# 1_Top_Sheet.net
KiCad netlist of a schematic drawn in Altium Designer
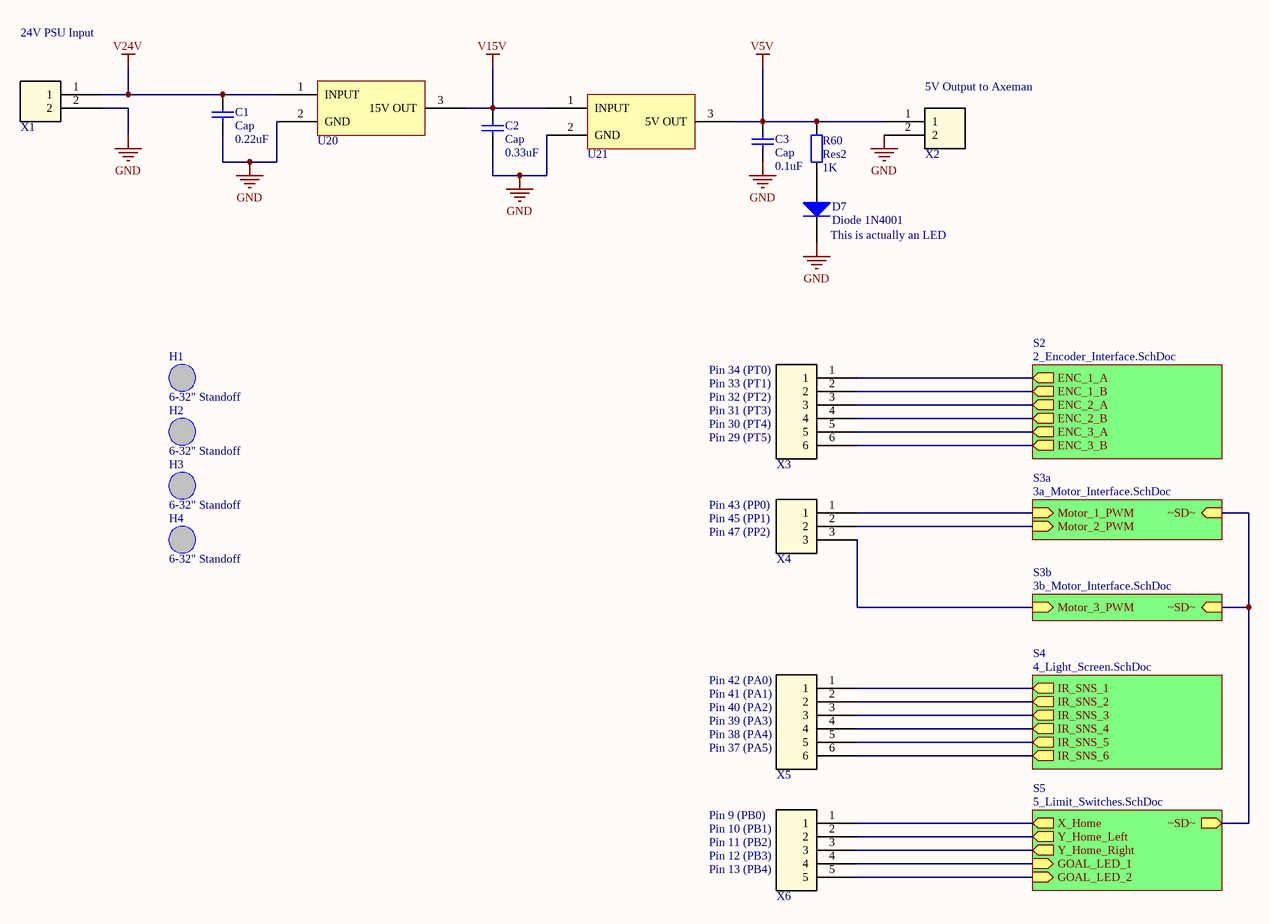
[diagram p0: 1_Top_Sheet.SchDoc]

(export (version "E")
  (design (tool "Eeschema 10.0.6"))
  (components
    (comp (ref "C1")
      (value "Cap")
      (footprint "RAD-0.3")
      (description "Capacitor")
      (fields (field (name "ALTIUM_VALUE") "0.22uF") (field (name "PUBLISHER") "Altium Limited"))
      (libsource (lib "Miscellaneous Devices") (part "Cap"))
    )
    (comp (ref "C2")
      (value "Cap")
      (footprint "RAD-0.3")
      (description "Capacitor")
      (fields (field (name "ALTIUM_VALUE") "0.33uF") (field (name "PUBLISHER") "Altium Limited"))
      (libsource (lib "Miscellaneous Devices") (part "Cap"))
    )
    (comp (ref "C3")
      (value "Cap")
      (footprint "RAD-0.3")
      (description "Capacitor")
      (fields (field (name "ALTIUM_VALUE") "0.1uF") (field (name "PUBLISHER") "Altium Limited"))
      (libsource (lib "Miscellaneous Devices") (part "Cap"))
    )
    (comp (ref "D7")
      (value "Diode 1N4001")
      (footprint "DO-41")
      (description "1 Amp General Purpose Rectifier")
      (fields (field (name "PUBLISHER") "Altium Limited"))
      (libsource (lib "Miscellaneous Devices") (part "Diode 1N4001"))
    )
    (comp (ref "H1")
      (value "6-32\" Standoff")
      (footprint "6-32\" Standoff")
      (description "Mounting hole for 6-32\" Standoff")
      (libsource (lib "thomas_lib") (part "6-32{dblquote} Standoff"))
    )
    (comp (ref "H2")
      (value "6-32\" Standoff")
      (footprint "6-32\" Standoff")
      (description "Mounting hole for 6-32\" Standoff")
      (libsource (lib "thomas_lib") (part "6-32{dblquote} Standoff"))
    )
    (comp (ref "H3")
      (value "6-32\" Standoff")
      (footprint "6-32\" Standoff")
      (description "Mounting hole for 6-32\" Standoff")
      (libsource (lib "thomas_lib") (part "6-32{dblquote} Standoff"))
    )
    (comp (ref "H4")
      (value "6-32\" Standoff")
      (footprint "6-32\" Standoff")
      (description "Mounting hole for 6-32\" Standoff")
      (libsource (lib "thomas_lib") (part "6-32{dblquote} Standoff"))
    )
    (comp (ref "R60")
      (value "Res2")
      (footprint "AXIAL-0.4")
      (description "Resistor")
      (fields (field (name "ALTIUM_VALUE") "1K") (field (name "PUBLISHER") "Altium Limited"))
      (libsource (lib "Miscellaneous Devices") (part "Res2"))
    )
    (comp (ref "U20")
      (value "IC REG LINEAR 15V 1A TO220-3")
      (footprint "thomas_lib:TO-220")
      (fields
        (field (name "MANUFACTURER_PART_NUMBER") "LM340T-15/NOPB")
        (field (name "MANUFACTURER") "Texas Instruments")
        (field (name "DIGI-KEY_PART_NUMBER") "LM340T-15/NOPB-ND")
      )
      (libsource (lib "thomas_lib") (part "IC REG LINEAR 15V 1A TO220-3"))
    )
    (comp (ref "U21")
      (value "IC REG LINEAR 5V 1.5A TO220-3")
      (footprint "thomas_lib:TO-220")
      (fields
        (field (name "MANUFACTURER_PART_NUMBER") "UA7805CKCS")
        (field (name "MANUFACTURER") "Texas Instruments")
        (field (name "DIGI-KEY_PART_NUMBER") "296-13996-5-ND")
      )
      (libsource (lib "thomas_lib") (part "IC REG LINEAR 5V 1.5A TO220-3"))
    )
    (comp (ref "X1")
      (value "TERM BLOCK HDR 2POS VERT 7.62MM")
      (footprint "PCV 4-2")
      (fields
        (field (name "DIGIKEY_PART_NUMBER") "277-1469-ND")
        (field (name "MANUFACTURER_PART_NUMBER") "1804687")
        (field (name "MANUFACTURER") "Phoenix Contact")
      )
      (libsource (lib "thomas_lib") (part "TERM BLOCK HDR 2POS VERT 7.62MM"))
    )
    (comp (ref "X2")
      (value "TERM BLOCK HDR 2POS VERT 3.5MM")
      (footprint "WR-TBL-3211 2")
      (fields
        (field (name "DIGIKEY_PART_NUMBER") "732-2763-ND")
        (field (name "MANUFACTURER_PART_NUMBER") "691321100002")
        (field (name "MANUFACTURER") "Wurth Electronics Inc")
      )
      (libsource (lib "thomas_lib") (part "TERM BLOCK HDR 2POS VERT 3.5MM"))
    )
    (comp (ref "X3")
      (value "TERM BLOCK HDR 6POS VERT 3.5MM")
      (footprint "WR-TBL-3211 6")
      (fields
        (field (name "DIGIKEY_PART_NUMBER") "732-2767-ND")
        (field (name "MANUFACTURER_PART_NUMBER") "691321100006")
        (field (name "MANUFACTURER") "Wurth Electronics Inc")
      )
      (libsource (lib "thomas_lib") (part "TERM BLOCK HDR 6POS VERT 3.5MM"))
    )
    (comp (ref "X4")
      (value "TERM BLOCK HDR 3POS VERT 3.5MM")
      (footprint "WR-TBL-3211 3")
      (fields
        (field (name "DIGIKEY_PART_NUMBER") "732-2764-ND")
        (field (name "MANUFACTURER_PART_NUMBER") "691321100003")
        (field (name "MANUFACTURER") "Wurth Electronics Inc")
      )
      (libsource (lib "thomas_lib") (part "TERM BLOCK HDR 3POS VERT 3.5MM"))
    )
    (comp (ref "X5")
      (value "TERM BLOCK HDR 6POS VERT 3.5MM")
      (footprint "WR-TBL-3211 6")
      (fields
        (field (name "DIGIKEY_PART_NUMBER") "732-2767-ND")
        (field (name "MANUFACTURER_PART_NUMBER") "691321100006")
        (field (name "MANUFACTURER") "Wurth Electronics Inc")
      )
      (libsource (lib "thomas_lib") (part "TERM BLOCK HDR 6POS VERT 3.5MM"))
    )
    (comp (ref "X6")
      (value "TERM BLOCK HDR 5POS VERT 3.5MM")
      (footprint "WR-TBL-3211 5")
      (fields
        (field (name "DIGIKEY_PART_NUMBER") "732-2766-ND")
        (field (name "MANUFACTURER_PART_NUMBER") "691321100005")
        (field (name "MANUFACTURER") "Wurth Electronics Inc")
      )
      (libsource (lib "thomas_lib") (part "TERM BLOCK HDR 5POS VERT 3.5MM"))
    )
  )
  (nets
    (net (code "1") (name "/ENC_1_A") (class "Default")
      (node (ref "X3") (pin "1") (pinfunction "1_1") (pintype "passive"))
    )
    (net (code "2") (name "/ENC_1_B") (class "Default")
      (node (ref "X3") (pin "2") (pinfunction "2_2") (pintype "passive"))
    )
    (net (code "3") (name "/ENC_2_A") (class "Default")
      (node (ref "X3") (pin "3") (pinfunction "3_3") (pintype "passive"))
    )
    (net (code "4") (name "/ENC_2_B") (class "Default")
      (node (ref "X3") (pin "4") (pinfunction "4_4") (pintype "passive"))
    )
    (net (code "5") (name "/ENC_3_A") (class "Default")
      (node (ref "X3") (pin "5") (pinfunction "5_5") (pintype "passive"))
    )
    (net (code "6") (name "/ENC_3_B") (class "Default")
      (node (ref "X3") (pin "6") (pinfunction "6_6") (pintype "passive"))
    )
    (net (code "7") (name "/GOAL_LED_1") (class "Default")
      (node (ref "X6") (pin "4") (pinfunction "4_4") (pintype "passive"))
    )
    (net (code "8") (name "/GOAL_LED_2") (class "Default")
      (node (ref "X6") (pin "5") (pinfunction "5_5") (pintype "passive"))
    )
    (net (code "9") (name "/IR_SNS_1") (class "Default")
      (node (ref "X5") (pin "1") (pinfunction "1_1") (pintype "passive"))
    )
    (net (code "10") (name "/IR_SNS_2") (class "Default")
      (node (ref "X5") (pin "2") (pinfunction "2_2") (pintype "passive"))
    )
    (net (code "11") (name "/IR_SNS_3") (class "Default")
      (node (ref "X5") (pin "3") (pinfunction "3_3") (pintype "passive"))
    )
    (net (code "12") (name "/IR_SNS_4") (class "Default")
      (node (ref "X5") (pin "4") (pinfunction "4_4") (pintype "passive"))
    )
    (net (code "13") (name "/IR_SNS_5") (class "Default")
      (node (ref "X5") (pin "5") (pinfunction "5_5") (pintype "passive"))
    )
    (net (code "14") (name "/IR_SNS_6") (class "Default")
      (node (ref "X5") (pin "6") (pinfunction "6_6") (pintype "passive"))
    )
    (net (code "15") (name "/Motor_1_PWM") (class "Default")
      (node (ref "X4") (pin "1") (pinfunction "1_1") (pintype "passive"))
    )
    (net (code "16") (name "/Motor_2_PWM") (class "Default")
      (node (ref "X4") (pin "2") (pinfunction "2_2") (pintype "passive"))
    )
    (net (code "17") (name "/Motor_3_PWM") (class "Default")
      (node (ref "X4") (pin "3") (pinfunction "3_3") (pintype "passive"))
    )
    (net (code "18") (name "/X_Home") (class "Default")
      (node (ref "X6") (pin "1") (pinfunction "1_1") (pintype "passive"))
    )
    (net (code "19") (name "/Y_Home_Left") (class "Default")
      (node (ref "X6") (pin "2") (pinfunction "2_2") (pintype "passive"))
    )
    (net (code "20") (name "/Y_Home_Right") (class "Default")
      (node (ref "X6") (pin "3") (pinfunction "3_3") (pintype "passive"))
    )
    (net (code "22") (name "GND") (class "Default")
      (node (ref "C1") (pin "1") (pinfunction "1_1") (pintype "passive"))
      (node (ref "C2") (pin "1") (pinfunction "1_1") (pintype "passive"))
      (node (ref "C3") (pin "1") (pinfunction "1_1") (pintype "passive"))
      (node (ref "D7") (pin "2") (pinfunction "K_2") (pintype "passive"))
      (node (ref "U20") (pin "2") (pinfunction "GND_2") (pintype "power_in"))
      (node (ref "U21") (pin "2") (pinfunction "GND_2") (pintype "power_in"))
      (node (ref "X1") (pin "2") (pinfunction "2_2") (pintype "passive"))
      (node (ref "X2") (pin "2") (pinfunction "2_2") (pintype "passive"))
    )
    (net (code "23") (name "Net-(D7-A)") (class "Default")
      (node (ref "D7") (pin "1") (pinfunction "A_1") (pintype "passive"))
      (node (ref "R60") (pin "1") (pinfunction "1_1") (pintype "passive"))
    )
    (net (code "24") (name "V5V") (class "Default")
      (node (ref "C3") (pin "2") (pinfunction "2_2") (pintype "passive"))
      (node (ref "R60") (pin "2") (pinfunction "2_2") (pintype "passive"))
      (node (ref "U21") (pin "3") (pinfunction "5V_OUT_3") (pintype "power_in"))
      (node (ref "X2") (pin "1") (pinfunction "1_1") (pintype "passive"))
    )
    (net (code "25") (name "V15V") (class "Default")
      (node (ref "C2") (pin "2") (pinfunction "2_2") (pintype "passive"))
      (node (ref "U20") (pin "3") (pinfunction "15V_OUT_3") (pintype "power_in"))
      (node (ref "U21") (pin "1") (pinfunction "INPUT_1") (pintype "power_in"))
    )
    (net (code "26") (name "V24V") (class "Default")
      (node (ref "C1") (pin "2") (pinfunction "2_2") (pintype "passive"))
      (node (ref "U20") (pin "1") (pinfunction "INPUT_1") (pintype "power_in"))
      (node (ref "X1") (pin "1") (pinfunction "1_1") (pintype "passive"))
    )
  )
)
